# testPresssureSensor.net
KiCad netlist of a schematic drawn in EAGLE
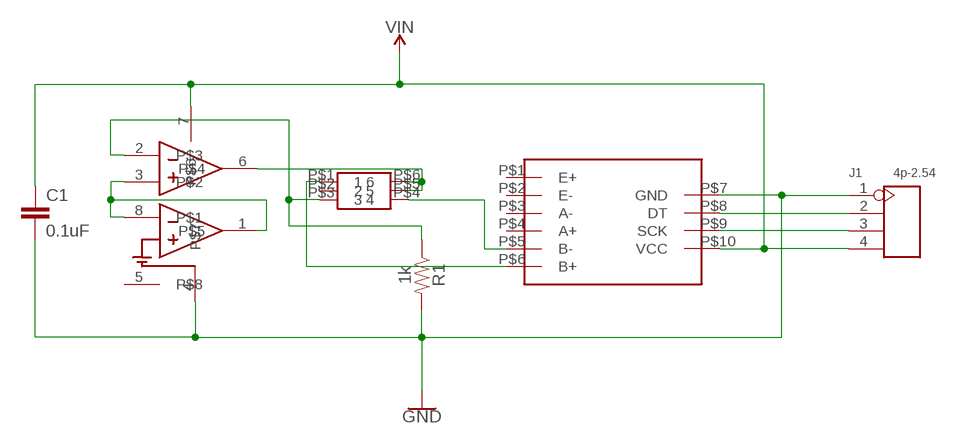
[diagram p0: schematic, sheet 1]

(export (version "E")
  (design (tool "Eeschema 10.0.6"))
  (components
    (comp (ref "C1")
      (value "0.1uF")
      (footprint "eagle-import:0603")
      (libsource (lib "eagle-import") (part "0.1UF-0603-25V-(+80/-20%)"))
    )
    (comp (ref "J1")
      (value "4p-2.54")
      (footprint "eagle-import:H4-2.54")
      (fields (field (name "MPN") "P125-1104A0BS116A1"))
      (libsource (lib "eagle-import") (part "DIP-BLACK-MALE-HEADER-VERT(4P-2.54)"))
    )
    (comp (ref "R1")
      (value "1k")
      (footprint "eagle-import:AXIAL-0.3")
      (libsource (lib "eagle-import") (part "1KOHM-HORIZ-1/4W-1%"))
    )
    (comp (ref "U$1")
      (value "2SMPP-03")
      (footprint "eagle-import:2SMPP-03")
      (libsource (lib "eagle-import") (part "2SMPP-03"))
    )
    (comp (ref "U$2")
      (value "HX711")
      (footprint "eagle-import:HX711")
      (libsource (lib "eagle-import") (part "HX711"))
    )
    (comp (ref "U$3")
      (value "LM10CN")
      (footprint "eagle-import:DIP8")
      (libsource (lib "eagle-import") (part "LM10CN"))
    )
  )
  (nets
    (net (code "1") (name "GND") (class "Default")
      (node (ref "C1") (pin "2") (pinfunction "2_2") (pintype "passive"))
      (node (ref "J1") (pin "1") (pinfunction "P$1_1") (pintype "bidirectional"))
      (node (ref "R1") (pin "P$2") (pinfunction "2_P$2") (pintype "passive"))
      (node (ref "U$2") (pin "P$7") (pinfunction "GND_P$7") (pintype "bidirectional"))
      (node (ref "U$3") (pin "4") (pinfunction "P$7_4") (pintype "bidirectional"))
    )
    (net (code "2") (name "Net-(J1-P$2)") (class "Default")
      (node (ref "J1") (pin "2") (pinfunction "P$2_2") (pintype "bidirectional"))
      (node (ref "U$2") (pin "P$8") (pinfunction "DT_P$8") (pintype "bidirectional"))
    )
    (net (code "3") (name "Net-(J1-P$3)") (class "Default")
      (node (ref "J1") (pin "3") (pinfunction "P$3_3") (pintype "bidirectional"))
      (node (ref "U$2") (pin "P$9") (pinfunction "SCK_P$9") (pintype "bidirectional"))
    )
    (net (code "4") (name "Net-(R1-1)") (class "Default")
      (node (ref "R1") (pin "P$1") (pinfunction "1_P$1") (pintype "passive"))
      (node (ref "U$1") (pin "P$3") (pinfunction "3_P$3") (pintype "bidirectional"))
      (node (ref "U$3") (pin "2") (pinfunction "P$3_2") (pintype "bidirectional"))
    )
    (net (code "5") (name "Net-(U$1-1)") (class "Default")
      (node (ref "U$1") (pin "P$1") (pinfunction "1_P$1") (pintype "bidirectional"))
      (node (ref "U$2") (pin "P$6") (pinfunction "B+_P$6") (pintype "bidirectional"))
    )
    (net (code "6") (name "Net-(U$1-4)") (class "Default")
      (node (ref "U$1") (pin "P$4") (pinfunction "4_P$4") (pintype "bidirectional"))
      (node (ref "U$2") (pin "P$5") (pinfunction "B-_P$5") (pintype "bidirectional"))
    )
    (net (code "7") (name "Net-(U$1-5)") (class "Default")
      (node (ref "U$1") (pin "P$5") (pinfunction "5_P$5") (pintype "bidirectional"))
      (node (ref "U$1") (pin "P$6") (pinfunction "6_P$6") (pintype "bidirectional"))
      (node (ref "U$3") (pin "6") (pinfunction "P$4_6") (pintype "bidirectional"))
    )
    (net (code "8") (name "Net-(U$3-P$1)") (class "Default")
      (node (ref "U$3") (pin "1") (pinfunction "P$5_1") (pintype "bidirectional"))
      (node (ref "U$3") (pin "3") (pinfunction "P$2_3") (pintype "bidirectional"))
      (node (ref "U$3") (pin "8") (pinfunction "P$1_8") (pintype "bidirectional"))
    )
    (net (code "9") (name "VIN") (class "Default")
      (node (ref "C1") (pin "1") (pinfunction "1_1") (pintype "passive"))
      (node (ref "J1") (pin "4") (pinfunction "P$4_4") (pintype "bidirectional"))
      (node (ref "U$2") (pin "P$10") (pinfunction "VCC_P$10") (pintype "bidirectional"))
      (node (ref "U$3") (pin "7") (pinfunction "P$6_7") (pintype "bidirectional"))
    )
    (net (code "10") (name "unconnected-(U$1-2-PadP$2)") (class "Default")
      (node (ref "U$1") (pin "P$2") (pinfunction "2_P$2") (pintype "bidirectional"))
    )
    (net (code "11") (name "unconnected-(U$2-A+-PadP$4)") (class "Default")
      (node (ref "U$2") (pin "P$4") (pinfunction "A+_P$4") (pintype "bidirectional"))
    )
    (net (code "12") (name "unconnected-(U$2-A--PadP$3)") (class "Default")
      (node (ref "U$2") (pin "P$3") (pinfunction "A-_P$3") (pintype "bidirectional"))
    )
    (net (code "13") (name "unconnected-(U$2-E+-PadP$1)") (class "Default")
      (node (ref "U$2") (pin "P$1") (pinfunction "E+_P$1") (pintype "bidirectional"))
    )
    (net (code "14") (name "unconnected-(U$2-E--PadP$2)") (class "Default")
      (node (ref "U$2") (pin "P$2") (pinfunction "E-_P$2") (pintype "bidirectional"))
    )
    (net (code "15") (name "unconnected-(U$3-P$8-Pad5)") (class "Default")
      (node (ref "U$3") (pin "5") (pinfunction "P$8_5") (pintype "bidirectional"))
    )
  )
)
